# Power_management.net
KiCad netlist of a schematic drawn in Altium Designer
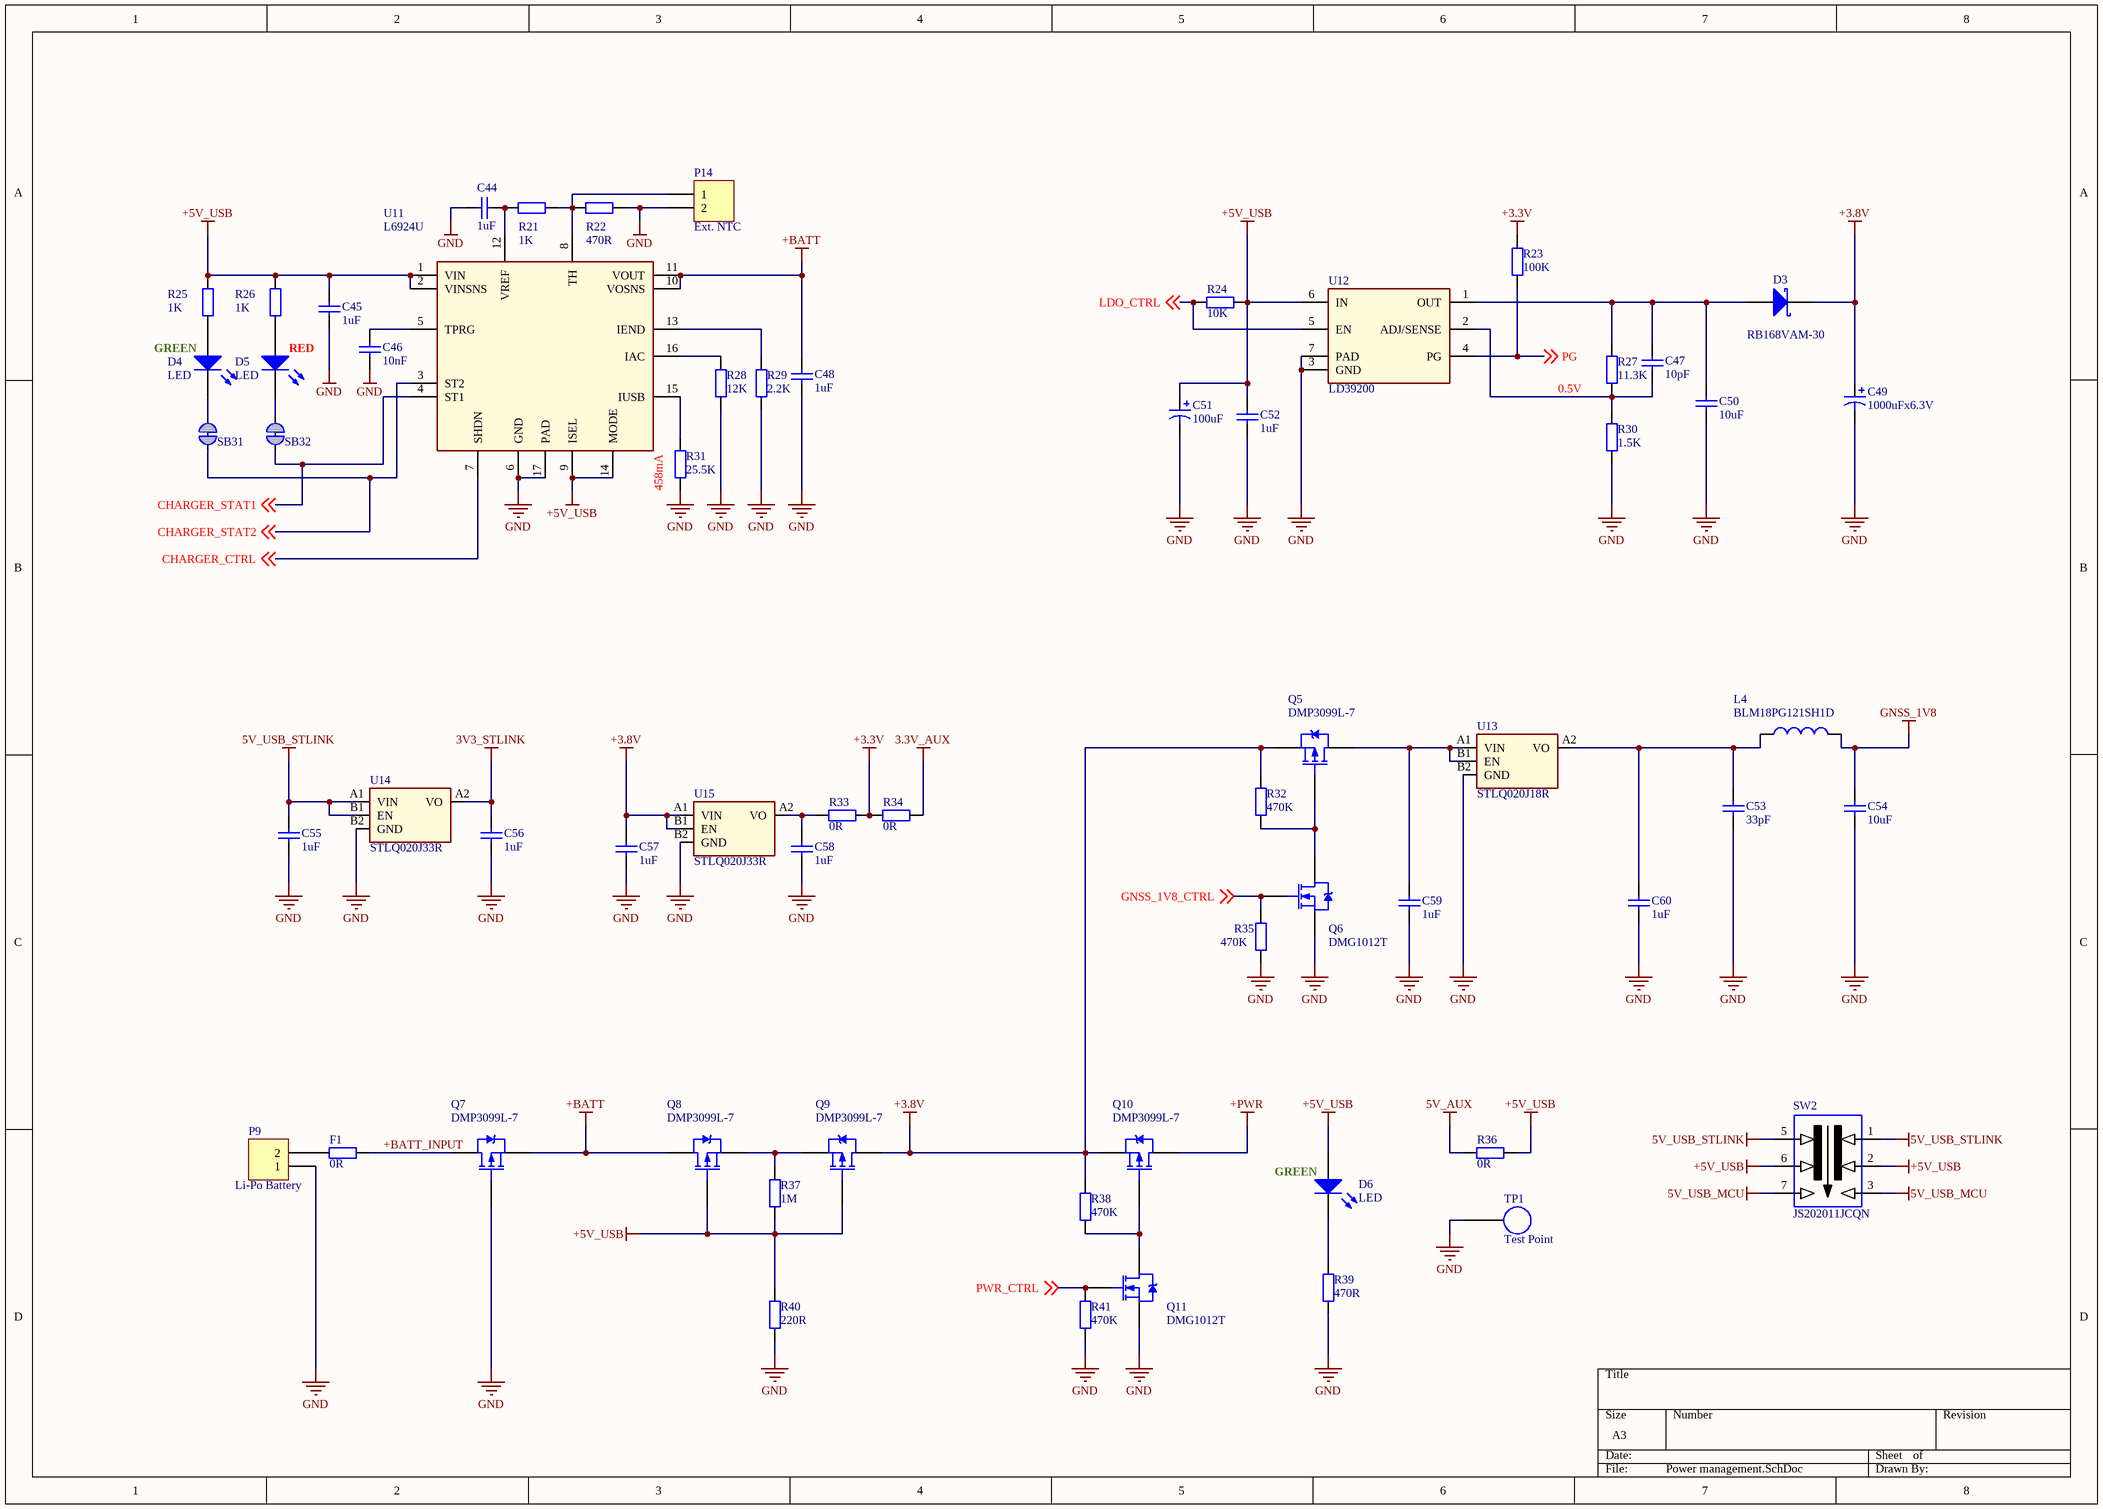
[diagram p0: Power management.SchDoc]

(export (version "E")
  (design (tool "Eeschema 10.0.6"))
  (components
    (comp (ref "C44")
      (value "1uF")
      (footprint "C0402")
      (description "Capacitor (Semiconductor SIM Model)")
      (fields
        (field (name "MANUFACTURER") "Samsung Electronics")
        (field (name "MANUFACTURER PART NO.") "CL05B102KB5NNND")
      )
      (libsource (lib "Miscellaneous Devices") (part "Cap Semi"))
    )
    (comp (ref "C45")
      (value "1uF")
      (footprint "C0402")
      (description "Capacitor (Semiconductor SIM Model)")
      (fields
        (field (name "MANUFACTURER") "Samsung Electronics")
        (field (name "MANUFACTURER PART NO.") "CL05B102KB5NNND")
      )
      (libsource (lib "Miscellaneous Devices") (part "Cap Semi"))
    )
    (comp (ref "C46")
      (value "10nF")
      (footprint "C0402")
      (description "Capacitor (Semiconductor SIM Model)")
      (fields
        (field (name "MANUFACTURER") "Samsung Electronics")
        (field (name "MANUFACTURER PART NO.") "CL05B102KB5NNND")
      )
      (libsource (lib "Miscellaneous Devices") (part "Cap Semi"))
    )
    (comp (ref "C47")
      (value "10pF")
      (footprint "C0402")
      (description "Capacitor (Semiconductor SIM Model)")
      (fields
        (field (name "MANUFACTURER") "YAGEO")
        (field (name "MANUFACTURER PART NO.") "CC0402JRNPO9BN100")
      )
      (libsource (lib "Miscellaneous Devices") (part "Cap Semi"))
    )
    (comp (ref "C48")
      (value "1uF")
      (footprint "C0402")
      (description "Capacitor (Semiconductor SIM Model)")
      (fields
        (field (name "MANUFACTURER") "Samsung Electronics")
        (field (name "MANUFACTURER PART NO.") "CL05B102KB5NNND")
      )
      (libsource (lib "Miscellaneous Devices") (part "Cap Semi"))
    )
    (comp (ref "C49")
      (value "1000uFx6.3V")
      (footprint "7361-38")
      (fields
        (field (name "MANUFACTURER") "AVX")
        (field (name "MANUFACTURER PART NO.") "TPSV108M006R0050")
        (field (name "Comment") "electrolytic capacitor")
      )
      (libsource (lib "Miscellaneous Devices") (part "Cap Pol1"))
    )
    (comp (ref "C50")
      (value "10uF")
      (footprint "C0402")
      (description "Capacitor (Semiconductor SIM Model)")
      (fields
        (field (name "MANUFACTURER") "Samsung Electronics")
        (field (name "MANUFACTURER PART NO.") "CL05A106MP5NUNC")
      )
      (libsource (lib "Miscellaneous Devices") (part "Cap Semi"))
    )
    (comp (ref "C51")
      (value "100uF")
      (footprint "Case-B")
      (fields
        (field (name "MANUFACTURER") "AVX")
        (field (name "MANUFACTURER PART NO.") "TPSB107K006R0400")
        (field (name "Comment") "electrolytic capacitor")
      )
      (libsource (lib "Miscellaneous Devices") (part "Cap Pol1"))
    )
    (comp (ref "C52")
      (value "1uF")
      (footprint "C0402")
      (description "Capacitor (Semiconductor SIM Model)")
      (fields
        (field (name "MANUFACTURER") "Samsung Electronics")
        (field (name "MANUFACTURER PART NO.") "CL05A106MP5NUNC")
      )
      (libsource (lib "Miscellaneous Devices") (part "Cap Semi"))
    )
    (comp (ref "C53")
      (value "33pF")
      (footprint "C0402")
      (description "Capacitor (Semiconductor SIM Model)")
      (fields (field (name "MANUFACTURER") "AVX") (field (name "MANUFACTURER PART NO.") "04025A330JAT2A"))
      (libsource (lib "Miscellaneous Devices") (part "Cap Semi"))
    )
    (comp (ref "C54")
      (value "10uF")
      (footprint "C0402")
      (description "Capacitor (Semiconductor SIM Model)")
      (fields
        (field (name "MANUFACTURER") "Samsung Electronics")
        (field (name "MANUFACTURER PART NO.") "CL05A106MP5NUNC")
      )
      (libsource (lib "Miscellaneous Devices") (part "Cap Semi"))
    )
    (comp (ref "C55")
      (value "1uF")
      (footprint "C0402")
      (description "Capacitor (Semiconductor SIM Model)")
      (fields
        (field (name "MANUFACTURER") "Samsung Electronics")
        (field (name "MANUFACTURER PART NO.") "CL05A225MQ5NNNC")
      )
      (libsource (lib "Miscellaneous Devices") (part "Cap Semi"))
    )
    (comp (ref "C56")
      (value "1uF")
      (footprint "C0402")
      (description "Capacitor (Semiconductor SIM Model)")
      (fields
        (field (name "MANUFACTURER") "Samsung Electronics")
        (field (name "MANUFACTURER PART NO.") "CL05A225MQ5NNNC")
      )
      (libsource (lib "Miscellaneous Devices") (part "Cap Semi"))
    )
    (comp (ref "C57")
      (value "1uF")
      (footprint "C0402")
      (description "Capacitor (Semiconductor SIM Model)")
      (fields
        (field (name "MANUFACTURER") "Samsung Electronics")
        (field (name "MANUFACTURER PART NO.") "CL05A225MQ5NNNC")
      )
      (libsource (lib "Miscellaneous Devices") (part "Cap Semi"))
    )
    (comp (ref "C58")
      (value "1uF")
      (footprint "C0402")
      (description "Capacitor (Semiconductor SIM Model)")
      (fields
        (field (name "MANUFACTURER") "Samsung Electronics")
        (field (name "MANUFACTURER PART NO.") "CL05A225MQ5NNNC")
      )
      (libsource (lib "Miscellaneous Devices") (part "Cap Semi"))
    )
    (comp (ref "C59")
      (value "1uF")
      (footprint "C0402")
      (description "Capacitor (Semiconductor SIM Model)")
      (fields
        (field (name "MANUFACTURER") "Samsung Electronics")
        (field (name "MANUFACTURER PART NO.") "CL05A225MQ5NNNC")
      )
      (libsource (lib "Miscellaneous Devices") (part "Cap Semi"))
    )
    (comp (ref "C60")
      (value "1uF")
      (footprint "C0402")
      (description "Capacitor (Semiconductor SIM Model)")
      (fields
        (field (name "MANUFACTURER") "Samsung Electronics")
        (field (name "MANUFACTURER PART NO.") "CL05A225MQ5NNNC")
      )
      (libsource (lib "Miscellaneous Devices") (part "Cap Semi"))
    )
    (comp (ref "D3")
      (value "RB168VAM-30")
      (footprint "SOD323")
      (description "Schottky Diode")
      (fields (field (name "MANUFACTURER") "ROHM"))
      (libsource (lib "Miscellaneous Devices") (part "D Schottky"))
    )
    (comp (ref "D4")
      (value "LED")
      (footprint "PICOLED")
      (description "Typical SMD LED")
      (fields (field (name "MANUFACTURER") "ROHM") (field (name "MANUFACTURER PART NO.") "SML-P13PTT86R"))
      (libsource (lib "Miscellaneous Devices") (part "LED2"))
    )
    (comp (ref "D5")
      (value "LED")
      (footprint "PICOLED")
      (description "Typical SMD LED")
      (fields (field (name "MANUFACTURER") "ROHM") (field (name "MANUFACTURER PART NO.") "SML-P12UTT86"))
      (libsource (lib "Miscellaneous Devices") (part "LED2"))
    )
    (comp (ref "D6")
      (value "LED")
      (footprint "PICOLED")
      (description "Typical SMD LED")
      (fields (field (name "MANUFACTURER") "ROHM") (field (name "MANUFACTURER PART NO.") "SML-P13PTT86R"))
      (libsource (lib "Miscellaneous Devices") (part "LED2"))
    )
    (comp (ref "F1")
      (value "0R")
      (footprint "R0603")
      (fields
        (field (name "MANUFACTURER") "YAGEO")
        (field (name "MANUFACTURER PART NO.") "RC0402FR-070RL")
        (field (name "Comment") "Res2")
      )
      (libsource (lib "") (part "Res2_3"))
    )
    (comp (ref "L4")
      (value "BLM18PG121SH1D")
      (footprint "L0603")
      (description "Inductor")
      (fields (field (name "MANUFACTURER") "muRata"))
      (libsource (lib "Miscellaneous Devices") (part "Inductor"))
    )
    (comp (ref "P9")
      (value "Li-Po Battery")
      (footprint "104238-0210  Molex")
      (fields (field (name "MANUFACTURER") "Molex") (field (name "MANUFACTURER PART NO.") "104238-0210"))
      (libsource (lib "Miscellaneous Connectors") (part "Header 2"))
    )
    (comp (ref "P14")
      (value "Ext. NTC")
      (footprint "HDR1X2H")
      (description "Header, 2-Pin, Right Angle")
      (libsource (lib "Miscellaneous Connectors") (part "Header 2H"))
    )
    (comp (ref "Q5")
      (value "DMP3099L-7")
      (footprint "SOT23_custom")
      (fields (field (name "MANUFACTURER") "Diodes Inc."))
      (libsource (lib "IR Discrete MOSFET - Power") (part "IRF5NJ5305"))
    )
    (comp (ref "Q6")
      (value "DMG1012T")
      (footprint "SOT-523_custom")
      (description "N-Channel Power MOSFET")
      (fields (field (name "MANUFACTURER") "Diodes Inc.") (field (name "MANUFACTURER PART NO.") "DMG1012T-7"))
      (libsource (lib "Miscellaneous Devices") (part "NMOS-2"))
    )
    (comp (ref "Q7")
      (value "DMP3099L-7")
      (footprint "SOT23_custom")
      (fields (field (name "MANUFACTURER") "Diodes Inc."))
      (libsource (lib "IR Discrete MOSFET - Power") (part "IRF5NJ5305"))
    )
    (comp (ref "Q8")
      (value "DMP3099L-7")
      (footprint "SOT23_custom")
      (fields (field (name "MANUFACTURER") "Diodes Inc."))
      (libsource (lib "IR Discrete MOSFET - Power") (part "IRF5NJ5305"))
    )
    (comp (ref "Q9")
      (value "DMP3099L-7")
      (footprint "SOT23_custom")
      (fields (field (name "MANUFACTURER") "Diodes Inc."))
      (libsource (lib "IR Discrete MOSFET - Power") (part "IRF5NJ5305"))
    )
    (comp (ref "Q10")
      (value "DMP3099L-7")
      (footprint "SOT23_custom")
      (fields (field (name "MANUFACTURER") "Diodes Inc."))
      (libsource (lib "IR Discrete MOSFET - Power") (part "IRF5NJ5305"))
    )
    (comp (ref "Q11")
      (value "DMG1012T")
      (footprint "SOT-523_custom")
      (description "N-Channel Power MOSFET")
      (fields (field (name "MANUFACTURER") "Diodes Inc.") (field (name "MANUFACTURER PART NO.") "DMG1012T-7"))
      (libsource (lib "Miscellaneous Devices") (part "NMOS-2"))
    )
    (comp (ref "R21")
      (value "1K")
      (footprint "R0402")
      (fields
        (field (name "MANUFACTURER") "ASJ")
        (field (name "MANUFACTURER PART NO.") "CR10-471-JK")
        (field (name "Comment") "Res2")
      )
      (libsource (lib "") (part "Res2_3"))
    )
    (comp (ref "R22")
      (value "470R")
      (footprint "R0402")
      (fields
        (field (name "MANUFACTURER") "ASJ")
        (field (name "MANUFACTURER PART NO.") "CR10-471-JK")
        (field (name "Comment") "Res2")
      )
      (libsource (lib "") (part "Res2_3"))
    )
    (comp (ref "R23")
      (value "100K")
      (footprint "R0402")
      (fields
        (field (name "MANUFACTURER") "ASJ")
        (field (name "MANUFACTURER PART NO.") "CR10-104-JK")
        (field (name "Comment") "Res2")
      )
      (libsource (lib "") (part "Res2_1"))
    )
    (comp (ref "R24")
      (value "10K")
      (footprint "R0402")
      (fields
        (field (name "MANUFACTURER") "ASJ")
        (field (name "MANUFACTURER PART NO.") "CR10-103-JK")
        (field (name "Comment") "Res2")
      )
      (libsource (lib "") (part "Res2_3"))
    )
    (comp (ref "R25")
      (value "1K")
      (footprint "R0402")
      (fields
        (field (name "MANUFACTURER") "ASJ")
        (field (name "MANUFACTURER PART NO.") "CR10-471-JK")
        (field (name "Comment") "Res2")
      )
      (libsource (lib "Miscellaneous Devices") (part "Res2"))
    )
    (comp (ref "R26")
      (value "1K")
      (footprint "R0402")
      (fields
        (field (name "MANUFACTURER") "ASJ")
        (field (name "MANUFACTURER PART NO.") "CR10-471-JK")
        (field (name "Comment") "Res2")
      )
      (libsource (lib "Miscellaneous Devices") (part "Res2"))
    )
    (comp (ref "R27")
      (value "11.3K")
      (footprint "R0402")
      (fields
        (field (name "MANUFACTURER") "ASJ")
        (field (name "MANUFACTURER PART NO.") "CR10-103-JK")
        (field (name "Comment") "Res2")
      )
      (libsource (lib "Miscellaneous Devices") (part "Res2"))
    )
    (comp (ref "R28")
      (value "12K")
      (footprint "R0402")
      (fields
        (field (name "MANUFACTURER") "ASJ")
        (field (name "MANUFACTURER PART NO.") "CR10-471-JK")
        (field (name "Comment") "Res2")
      )
      (libsource (lib "Miscellaneous Devices") (part "Res2"))
    )
    (comp (ref "R29")
      (value "2.2K")
      (footprint "R0402")
      (fields
        (field (name "MANUFACTURER") "ASJ")
        (field (name "MANUFACTURER PART NO.") "CR10-471-JK")
        (field (name "Comment") "Res2")
      )
      (libsource (lib "Miscellaneous Devices") (part "Res2"))
    )
    (comp (ref "R30")
      (value "1.5K")
      (footprint "R0402")
      (fields
        (field (name "MANUFACTURER") "YAGEO")
        (field (name "MANUFACTURER PART NO.") "RC0402JR-071K5L")
        (field (name "Comment") "Res2")
      )
      (libsource (lib "Miscellaneous Devices") (part "Res2"))
    )
    (comp (ref "R31")
      (value "25.5K")
      (footprint "R0402")
      (fields
        (field (name "MANUFACTURER") "ASJ")
        (field (name "MANUFACTURER PART NO.") "CR10-471-JK")
        (field (name "Comment") "Res2")
      )
      (libsource (lib "Miscellaneous Devices") (part "Res2"))
    )
    (comp (ref "R32")
      (value "470K")
      (footprint "R0402")
      (fields
        (field (name "MANUFACTURER") "ASJ")
        (field (name "MANUFACTURER PART NO.") "CR10-474-JK")
        (field (name "Comment") "Res2")
      )
      (libsource (lib "") (part "Res2_1"))
    )
    (comp (ref "R33")
      (value "0R")
      (footprint "R0402")
      (fields
        (field (name "MANUFACTURER") "YAGEO")
        (field (name "MANUFACTURER PART NO.") "RC0402FR-070RL")
        (field (name "Comment") "Res2")
      )
      (libsource (lib "") (part "Res2_2"))
    )
    (comp (ref "R34")
      (value "0R")
      (footprint "R0402")
      (fields
        (field (name "MANUFACTURER") "YAGEO")
        (field (name "MANUFACTURER PART NO.") "RC0402FR-070RL")
        (field (name "Comment") "Res2")
      )
      (libsource (lib "") (part "Res2_2"))
    )
    (comp (ref "R35")
      (value "470K")
      (footprint "R0402")
      (fields
        (field (name "MANUFACTURER") "ASJ")
        (field (name "MANUFACTURER PART NO.") "CR10-474-JK")
        (field (name "Comment") "Res2")
      )
      (libsource (lib "") (part "Res2_1"))
    )
    (comp (ref "R36")
      (value "0R")
      (footprint "R0402")
      (fields
        (field (name "MANUFACTURER") "YAGEO")
        (field (name "MANUFACTURER PART NO.") "RC0402FR-070RL")
        (field (name "Comment") "Res2")
      )
      (libsource (lib "") (part "Res2_2"))
    )
    (comp (ref "R37")
      (value "1M")
      (footprint "R0402")
      (fields
        (field (name "MANUFACTURER") "ASJ")
        (field (name "MANUFACTURER PART NO.") "CR10-105-JK")
        (field (name "Comment") "Res2")
      )
      (libsource (lib "Miscellaneous Devices") (part "Res2"))
    )
    (comp (ref "R38")
      (value "470K")
      (footprint "R0402")
      (fields
        (field (name "MANUFACTURER") "ASJ")
        (field (name "MANUFACTURER PART NO.") "CR10-474-JK")
        (field (name "Comment") "Res2")
      )
      (libsource (lib "") (part "Res2_1"))
    )
    (comp (ref "R39")
      (value "470R")
      (footprint "R0402")
      (fields
        (field (name "MANUFACTURER") "ASJ")
        (field (name "MANUFACTURER PART NO.") "CR10-471-JK")
        (field (name "Comment") "Res2")
      )
      (libsource (lib "Miscellaneous Devices") (part "Res2"))
    )
    (comp (ref "R40")
      (value "220R")
      (footprint "R0402")
      (fields
        (field (name "MANUFACTURER") "ASJ")
        (field (name "MANUFACTURER PART NO.") "CR10-221-JK")
        (field (name "Comment") "Res2")
      )
      (libsource (lib "") (part "Res2_1"))
    )
    (comp (ref "R41")
      (value "470K")
      (footprint "R0402")
      (fields
        (field (name "MANUFACTURER") "ASJ")
        (field (name "MANUFACTURER PART NO.") "CR10-474-JK")
        (field (name "Comment") "Res2")
      )
      (libsource (lib "") (part "Res2_1"))
    )
    (comp (ref "SB31")
      (value "Solderbridge")
      (footprint "Solderbridge_Shorted")
      (libsource (lib "altium-import") (part "root_1_SOLDERBRIDGE_SHORTED_"))
    )
    (comp (ref "SB32")
      (value "Solderbridge")
      (footprint "Solderbridge_Shorted")
      (libsource (lib "altium-import") (part "root_1_SOLDERBRIDGE_SHORTED_"))
    )
    (comp (ref "SW2")
      (value "JS202011JCQN")
      (footprint "JS202011JCQN")
      (description "Sub-Miniature Slide Switch, VERTICAL MOUNT SMT - J BEND")
      (fields (field (name "MANUFACTURER") "CK Switches"))
      (libsource (lib "JS202011JCQN") (part "JS202011JCQN"))
    )
    (comp (ref "TP1")
      (value "Test Point")
      (footprint "5019_keystone")
      (description "SMD Test Point")
      (fields
        (field (name "MANUFACTURER") "Keystone Electrincs")
        (field (name "MANUFACTURER PART NO.") "5019")
      )
      (libsource (lib "test_point") (part "5019"))
    )
    (comp (ref "U11")
      (value "L6924U")
      (footprint "VFQFPN16")
      (description "Battery charger system\r\nwith integrated power switch for Li-Ion/Li-Polymer")
      (fields (field (name "MANUFACTURER") "STMicroelectronics"))
      (libsource (lib "RUT2CLOUDPrjPcb") (part "L6924D"))
    )
    (comp (ref "U12")
      (value "LD39200")
      (footprint "DFN6")
      (description "2 A high PSRR ultra low drop linear regulator with reverse current protection")
      (fields
        (field (name "MANUFACTURER") "STMicroelectronics")
        (field (name "MANUFACTURER PART NO.") "LD39200PUR")
      )
      (libsource (lib "RUT2CLOUDPrjPcb") (part "LD39200"))
    )
    (comp (ref "U13")
      (value "STLQ020J18R")
      (footprint "Flip-Chip4")
      (description "LDO")
      (fields (field (name "MANUFACTURER") "STMicroelectronics"))
      (libsource (lib "RUTLEO") (part "STLQ020"))
    )
    (comp (ref "U14")
      (value "STLQ020J33R")
      (footprint "Flip-Chip4")
      (description "LDO")
      (fields (field (name "MANUFACTURER") "STMicroelectronics"))
      (libsource (lib "RUTLEO") (part "STLQ020"))
    )
    (comp (ref "U15")
      (value "STLQ020J33R")
      (footprint "Flip-Chip4")
      (description "LDO")
      (fields (field (name "MANUFACTURER") "STMicroelectronics"))
      (libsource (lib "RUTLEO") (part "STLQ020"))
    )
  )
  (nets
    (net (code "1") (name "+3.3V") (class "Default")
      (node (ref "R23") (pin "2") (pinfunction "2_2") (pintype "passive"))
      (node (ref "R33") (pin "1") (pinfunction "1_1") (pintype "passive"))
      (node (ref "R34") (pin "2") (pinfunction "2_2") (pintype "passive"))
    )
    (net (code "2") (name "+3.8V") (class "Default")
      (node (ref "C49") (pin "1") (pinfunction "1_1") (pintype "passive"))
      (node (ref "C57") (pin "1") (pinfunction "1_1") (pintype "passive"))
      (node (ref "D3") (pin "2") (pinfunction "K_2") (pintype "passive"))
      (node (ref "Q10") (pin "3") (pinfunction "S_3") (pintype "passive"))
      (node (ref "Q5") (pin "3") (pinfunction "S_3") (pintype "passive"))
      (node (ref "Q9") (pin "1") (pinfunction "D_1") (pintype "passive"))
      (node (ref "R32") (pin "2") (pinfunction "2_2") (pintype "passive"))
      (node (ref "R38") (pin "2") (pinfunction "2_2") (pintype "passive"))
      (node (ref "U15") (pin "A1") (pinfunction "VIN_A1") (pintype "passive"))
      (node (ref "U15") (pin "B1") (pinfunction "EN_B1") (pintype "passive"))
    )
    (net (code "3") (name "+5V_USB") (class "Default")
      (node (ref "C45") (pin "1") (pinfunction "1_1") (pintype "passive"))
      (node (ref "C51") (pin "1") (pinfunction "1_1") (pintype "passive"))
      (node (ref "C52") (pin "2") (pinfunction "2_2") (pintype "passive"))
      (node (ref "D6") (pin "1") (pinfunction "A_1") (pintype "passive"))
      (node (ref "Q8") (pin "2") (pinfunction "G_2") (pintype "passive"))
      (node (ref "Q9") (pin "2") (pinfunction "G_2") (pintype "passive"))
      (node (ref "R24") (pin "2") (pinfunction "2_2") (pintype "passive"))
      (node (ref "R25") (pin "1") (pinfunction "1_1") (pintype "passive"))
      (node (ref "R26") (pin "1") (pinfunction "1_1") (pintype "passive"))
      (node (ref "R36") (pin "1") (pinfunction "1_1") (pintype "passive"))
      (node (ref "R37") (pin "2") (pinfunction "2_2") (pintype "passive"))
      (node (ref "R40") (pin "2") (pinfunction "2_2") (pintype "passive"))
      (node (ref "SW2") (pin "2") (pinfunction "2_2") (pintype "passive"))
      (node (ref "SW2") (pin "6") (pinfunction "6_6") (pintype "passive"))
      (node (ref "U11") (pin "1") (pinfunction "VIN_1") (pintype "passive"))
      (node (ref "U11") (pin "14") (pinfunction "MODE_14") (pintype "passive"))
      (node (ref "U11") (pin "2") (pinfunction "VINSNS_2") (pintype "passive"))
      (node (ref "U11") (pin "9") (pinfunction "ISEL_9") (pintype "passive"))
      (node (ref "U12") (pin "6") (pinfunction "IN_6") (pintype "passive"))
    )
    (net (code "4") (name "+BATT") (class "Default")
      (node (ref "C48") (pin "1") (pinfunction "1_1") (pintype "passive"))
      (node (ref "Q7") (pin "3") (pinfunction "S_3") (pintype "passive"))
      (node (ref "Q8") (pin "1") (pinfunction "D_1") (pintype "passive"))
      (node (ref "U11") (pin "10") (pinfunction "VOSNS_10") (pintype "passive"))
      (node (ref "U11") (pin "11") (pinfunction "VOUT_11") (pintype "passive"))
    )
    (net (code "5") (name "+PWR") (class "Default")
      (node (ref "Q10") (pin "1") (pinfunction "D_1") (pintype "passive"))
    )
    (net (code "6") (name "/+BATT_INPUT") (class "Default")
      (node (ref "F1") (pin "2") (pinfunction "2_2") (pintype "passive"))
      (node (ref "Q7") (pin "1") (pinfunction "D_1") (pintype "passive"))
    )
    (net (code "7") (name "3.3V_AUX") (class "Default")
      (node (ref "R34") (pin "1") (pinfunction "1_1") (pintype "passive"))
    )
    (net (code "8") (name "3V3_STLINK") (class "Default")
      (node (ref "C56") (pin "1") (pinfunction "1_1") (pintype "passive"))
      (node (ref "U14") (pin "A2") (pinfunction "VO_A2") (pintype "passive"))
    )
    (net (code "9") (name "5V_AUX") (class "Default")
      (node (ref "R36") (pin "2") (pinfunction "2_2") (pintype "passive"))
    )
    (net (code "10") (name "5V_USB_MCU") (class "Default")
      (node (ref "SW2") (pin "3") (pinfunction "3_3") (pintype "passive"))
      (node (ref "SW2") (pin "7") (pinfunction "7_7") (pintype "passive"))
    )
    (net (code "11") (name "5V_USB_STLINK") (class "Default")
      (node (ref "C55") (pin "1") (pinfunction "1_1") (pintype "passive"))
      (node (ref "SW2") (pin "1") (pinfunction "1_1") (pintype "passive"))
      (node (ref "SW2") (pin "5") (pinfunction "5_5") (pintype "passive"))
      (node (ref "U14") (pin "A1") (pinfunction "VIN_A1") (pintype "passive"))
      (node (ref "U14") (pin "B1") (pinfunction "EN_B1") (pintype "passive"))
    )
    (net (code "12") (name "CHARGER_CTRL") (class "Default")
      (node (ref "U11") (pin "7") (pinfunction "SHDN_7") (pintype "passive"))
    )
    (net (code "13") (name "CHARGER_STAT1") (class "Default")
      (node (ref "SB32") (pin "2") (pinfunction "1_2") (pintype "passive"))
      (node (ref "U11") (pin "4") (pinfunction "ST1_4") (pintype "passive"))
    )
    (net (code "14") (name "CHARGER_STAT2") (class "Default")
      (node (ref "SB31") (pin "2") (pinfunction "1_2") (pintype "passive"))
      (node (ref "U11") (pin "3") (pinfunction "ST2_3") (pintype "passive"))
    )
    (net (code "15") (name "GND") (class "Default")
      (node (ref "C44") (pin "2") (pinfunction "2_2") (pintype "passive"))
      (node (ref "C45") (pin "2") (pinfunction "2_2") (pintype "passive"))
      (node (ref "C46") (pin "2") (pinfunction "2_2") (pintype "passive"))
      (node (ref "C48") (pin "2") (pinfunction "2_2") (pintype "passive"))
      (node (ref "C49") (pin "2") (pinfunction "2_2") (pintype "passive"))
      (node (ref "C50") (pin "1") (pinfunction "1_1") (pintype "passive"))
      (node (ref "C51") (pin "2") (pinfunction "2_2") (pintype "passive"))
      (node (ref "C52") (pin "1") (pinfunction "1_1") (pintype "passive"))
      (node (ref "C53") (pin "1") (pinfunction "1_1") (pintype "passive"))
      (node (ref "C54") (pin "2") (pinfunction "2_2") (pintype "passive"))
      (node (ref "C55") (pin "2") (pinfunction "2_2") (pintype "passive"))
      (node (ref "C56") (pin "2") (pinfunction "2_2") (pintype "passive"))
      (node (ref "C57") (pin "2") (pinfunction "2_2") (pintype "passive"))
      (node (ref "C58") (pin "2") (pinfunction "2_2") (pintype "passive"))
      (node (ref "C59") (pin "2") (pinfunction "2_2") (pintype "passive"))
      (node (ref "C60") (pin "2") (pinfunction "2_2") (pintype "passive"))
      (node (ref "P14") (pin "2") (pinfunction "2_2") (pintype "passive"))
      (node (ref "P9") (pin "1") (pinfunction "1_1") (pintype "passive"))
      (node (ref "Q11") (pin "3") (pinfunction "S_3") (pintype "passive"))
      (node (ref "Q6") (pin "3") (pinfunction "S_3") (pintype "passive"))
      (node (ref "Q7") (pin "2") (pinfunction "G_2") (pintype "passive"))
      (node (ref "R22") (pin "2") (pinfunction "2_2") (pintype "passive"))
      (node (ref "R28") (pin "2") (pinfunction "2_2") (pintype "passive"))
      (node (ref "R29") (pin "2") (pinfunction "2_2") (pintype "passive"))
      (node (ref "R30") (pin "2") (pinfunction "2_2") (pintype "passive"))
      (node (ref "R31") (pin "2") (pinfunction "2_2") (pintype "passive"))
      (node (ref "R35") (pin "1") (pinfunction "1_1") (pintype "passive"))
      (node (ref "R39") (pin "2") (pinfunction "2_2") (pintype "passive"))
      (node (ref "R40") (pin "1") (pinfunction "1_1") (pintype "passive"))
      (node (ref "R41") (pin "1") (pinfunction "1_1") (pintype "passive"))
      (node (ref "TP1") (pin "1") (pinfunction "1_1") (pintype "passive"))
      (node (ref "U11") (pin "17") (pinfunction "PAD_17") (pintype "passive"))
      (node (ref "U11") (pin "6") (pinfunction "GND_6") (pintype "passive"))
      (node (ref "U12") (pin "3") (pinfunction "GND_3") (pintype "passive"))
      (node (ref "U12") (pin "7") (pinfunction "PAD_7") (pintype "passive"))
      (node (ref "U13") (pin "B2") (pinfunction "GND_B2") (pintype "passive"))
      (node (ref "U14") (pin "B2") (pinfunction "GND_B2") (pintype "passive"))
      (node (ref "U15") (pin "B2") (pinfunction "GND_B2") (pintype "passive"))
    )
    (net (code "16") (name "GNSS_1V8") (class "Default")
      (node (ref "C54") (pin "1") (pinfunction "1_1") (pintype "passive"))
      (node (ref "L4") (pin "2") (pinfunction "2_2") (pintype "passive"))
    )
    (net (code "17") (name "GNSS_1V8_CTRL") (class "Default")
      (node (ref "Q6") (pin "1") (pinfunction "G_1") (pintype "passive"))
      (node (ref "R35") (pin "2") (pinfunction "2_2") (pintype "passive"))
    )
    (net (code "18") (name "LDO_CTRL") (class "Default")
      (node (ref "R24") (pin "1") (pinfunction "1_1") (pintype "passive"))
      (node (ref "U12") (pin "5") (pinfunction "EN_5") (pintype "passive"))
    )
    (net (code "19") (name "Net-(D3-A)") (class "Default")
      (node (ref "C47") (pin "2") (pinfunction "2_2") (pintype "passive"))
      (node (ref "C50") (pin "2") (pinfunction "2_2") (pintype "passive"))
      (node (ref "D3") (pin "1") (pinfunction "A_1") (pintype "passive"))
      (node (ref "R27") (pin "1") (pinfunction "1_1") (pintype "passive"))
      (node (ref "U12") (pin "1") (pinfunction "OUT_1") (pintype "passive"))
    )
    (net (code "20") (name "Net-(D4-A)") (class "Default")
      (node (ref "D4") (pin "1") (pinfunction "A_1") (pintype "passive"))
      (node (ref "R25") (pin "2") (pinfunction "2_2") (pintype "passive"))
    )
    (net (code "21") (name "Net-(D4-K)") (class "Default")
      (node (ref "D4") (pin "2") (pinfunction "K_2") (pintype "passive"))
      (node (ref "SB31") (pin "1") (pinfunction "0_1") (pintype "passive"))
    )
    (net (code "22") (name "Net-(D5-A)") (class "Default")
      (node (ref "D5") (pin "1") (pinfunction "A_1") (pintype "passive"))
      (node (ref "R26") (pin "2") (pinfunction "2_2") (pintype "passive"))
    )
    (net (code "23") (name "Net-(D5-K)") (class "Default")
      (node (ref "D5") (pin "2") (pinfunction "K_2") (pintype "passive"))
      (node (ref "SB32") (pin "1") (pinfunction "0_1") (pintype "passive"))
    )
    (net (code "24") (name "Net-(D6-K)") (class "Default")
      (node (ref "D6") (pin "2") (pinfunction "K_2") (pintype "passive"))
      (node (ref "R39") (pin "1") (pinfunction "1_1") (pintype "passive"))
    )
    (net (code "25") (name "Net-(F1-Pad1)") (class "Default")
      (node (ref "F1") (pin "1") (pinfunction "1_1") (pintype "passive"))
      (node (ref "P9") (pin "2") (pinfunction "2_2") (pintype "passive"))
    )
    (net (code "26") (name "Net-(Q5-D)") (class "Default")
      (node (ref "C59") (pin "1") (pinfunction "1_1") (pintype "passive"))
      (node (ref "Q5") (pin "1") (pinfunction "D_1") (pintype "passive"))
      (node (ref "U13") (pin "A1") (pinfunction "VIN_A1") (pintype "passive"))
      (node (ref "U13") (pin "B1") (pinfunction "EN_B1") (pintype "passive"))
    )
    (net (code "27") (name "Net-(Q5-G)") (class "Default")
      (node (ref "Q5") (pin "2") (pinfunction "G_2") (pintype "passive"))
      (node (ref "Q6") (pin "2") (pinfunction "D_2") (pintype "passive"))
      (node (ref "R32") (pin "1") (pinfunction "1_1") (pintype "passive"))
    )
    (net (code "28") (name "Net-(Q8-S)") (class "Default")
      (node (ref "Q8") (pin "3") (pinfunction "S_3") (pintype "passive"))
      (node (ref "Q9") (pin "3") (pinfunction "S_3") (pintype "passive"))
      (node (ref "R37") (pin "1") (pinfunction "1_1") (pintype "passive"))
    )
    (net (code "29") (name "Net-(Q10-G)") (class "Default")
      (node (ref "Q10") (pin "2") (pinfunction "G_2") (pintype "passive"))
      (node (ref "Q11") (pin "2") (pinfunction "D_2") (pintype "passive"))
      (node (ref "R38") (pin "1") (pinfunction "1_1") (pintype "passive"))
    )
    (net (code "30") (name "Net-(U11-IAC)") (class "Default")
      (node (ref "R28") (pin "1") (pinfunction "1_1") (pintype "passive"))
      (node (ref "U11") (pin "16") (pinfunction "IAC_16") (pintype "passive"))
    )
    (net (code "31") (name "Net-(U11-IEND)") (class "Default")
      (node (ref "R29") (pin "1") (pinfunction "1_1") (pintype "passive"))
      (node (ref "U11") (pin "13") (pinfunction "IEND_13") (pintype "passive"))
    )
    (net (code "32") (name "Net-(U11-IUSB)") (class "Default")
      (node (ref "R31") (pin "1") (pinfunction "1_1") (pintype "passive"))
      (node (ref "U11") (pin "15") (pinfunction "IUSB_15") (pintype "passive"))
    )
    (net (code "33") (name "Net-(U11-TH)") (class "Default")
      (node (ref "P14") (pin "1") (pinfunction "1_1") (pintype "passive"))
      (node (ref "R21") (pin "2") (pinfunction "2_2") (pintype "passive"))
      (node (ref "R22") (pin "1") (pinfunction "1_1") (pintype "passive"))
      (node (ref "U11") (pin "8") (pinfunction "TH_8") (pintype "passive"))
    )
    (net (code "34") (name "Net-(U11-TPRG)") (class "Default")
      (node (ref "C46") (pin "1") (pinfunction "1_1") (pintype "passive"))
      (node (ref "U11") (pin "5") (pinfunction "TPRG_5") (pintype "passive"))
    )
    (net (code "35") (name "Net-(U11-VREF)") (class "Default")
      (node (ref "C44") (pin "1") (pinfunction "1_1") (pintype "passive"))
      (node (ref "R21") (pin "1") (pinfunction "1_1") (pintype "passive"))
      (node (ref "U11") (pin "12") (pinfunction "VREF_12") (pintype "passive"))
    )
    (net (code "36") (name "Net-(U12-ADJ{slash}SENSE)") (class "Default")
      (node (ref "C47") (pin "1") (pinfunction "1_1") (pintype "passive"))
      (node (ref "R27") (pin "2") (pinfunction "2_2") (pintype "passive"))
      (node (ref "R30") (pin "1") (pinfunction "1_1") (pintype "passive"))
      (node (ref "U12") (pin "2") (pinfunction "ADJ/SENSE_2") (pintype "passive"))
    )
    (net (code "37") (name "Net-(U13-VO)") (class "Default")
      (node (ref "C53") (pin "2") (pinfunction "2_2") (pintype "passive"))
      (node (ref "C60") (pin "1") (pinfunction "1_1") (pintype "passive"))
      (node (ref "L4") (pin "1") (pinfunction "1_1") (pintype "passive"))
      (node (ref "U13") (pin "A2") (pinfunction "VO_A2") (pintype "passive"))
    )
    (net (code "38") (name "Net-(U15-VO)") (class "Default")
      (node (ref "C58") (pin "1") (pinfunction "1_1") (pintype "passive"))
      (node (ref "R33") (pin "2") (pinfunction "2_2") (pintype "passive"))
      (node (ref "U15") (pin "A2") (pinfunction "VO_A2") (pintype "passive"))
    )
    (net (code "39") (name "PG") (class "Default")
      (node (ref "R23") (pin "1") (pinfunction "1_1") (pintype "passive"))
      (node (ref "U12") (pin "4") (pinfunction "PG_4") (pintype "passive"))
    )
    (net (code "40") (name "PWR_CTRL") (class "Default")
      (node (ref "Q11") (pin "1") (pinfunction "G_1") (pintype "passive"))
      (node (ref "R41") (pin "2") (pinfunction "2_2") (pintype "passive"))
    )
  )
)
